# store-column-block.net
KiCad netlist of a schematic drawn in EAGLE
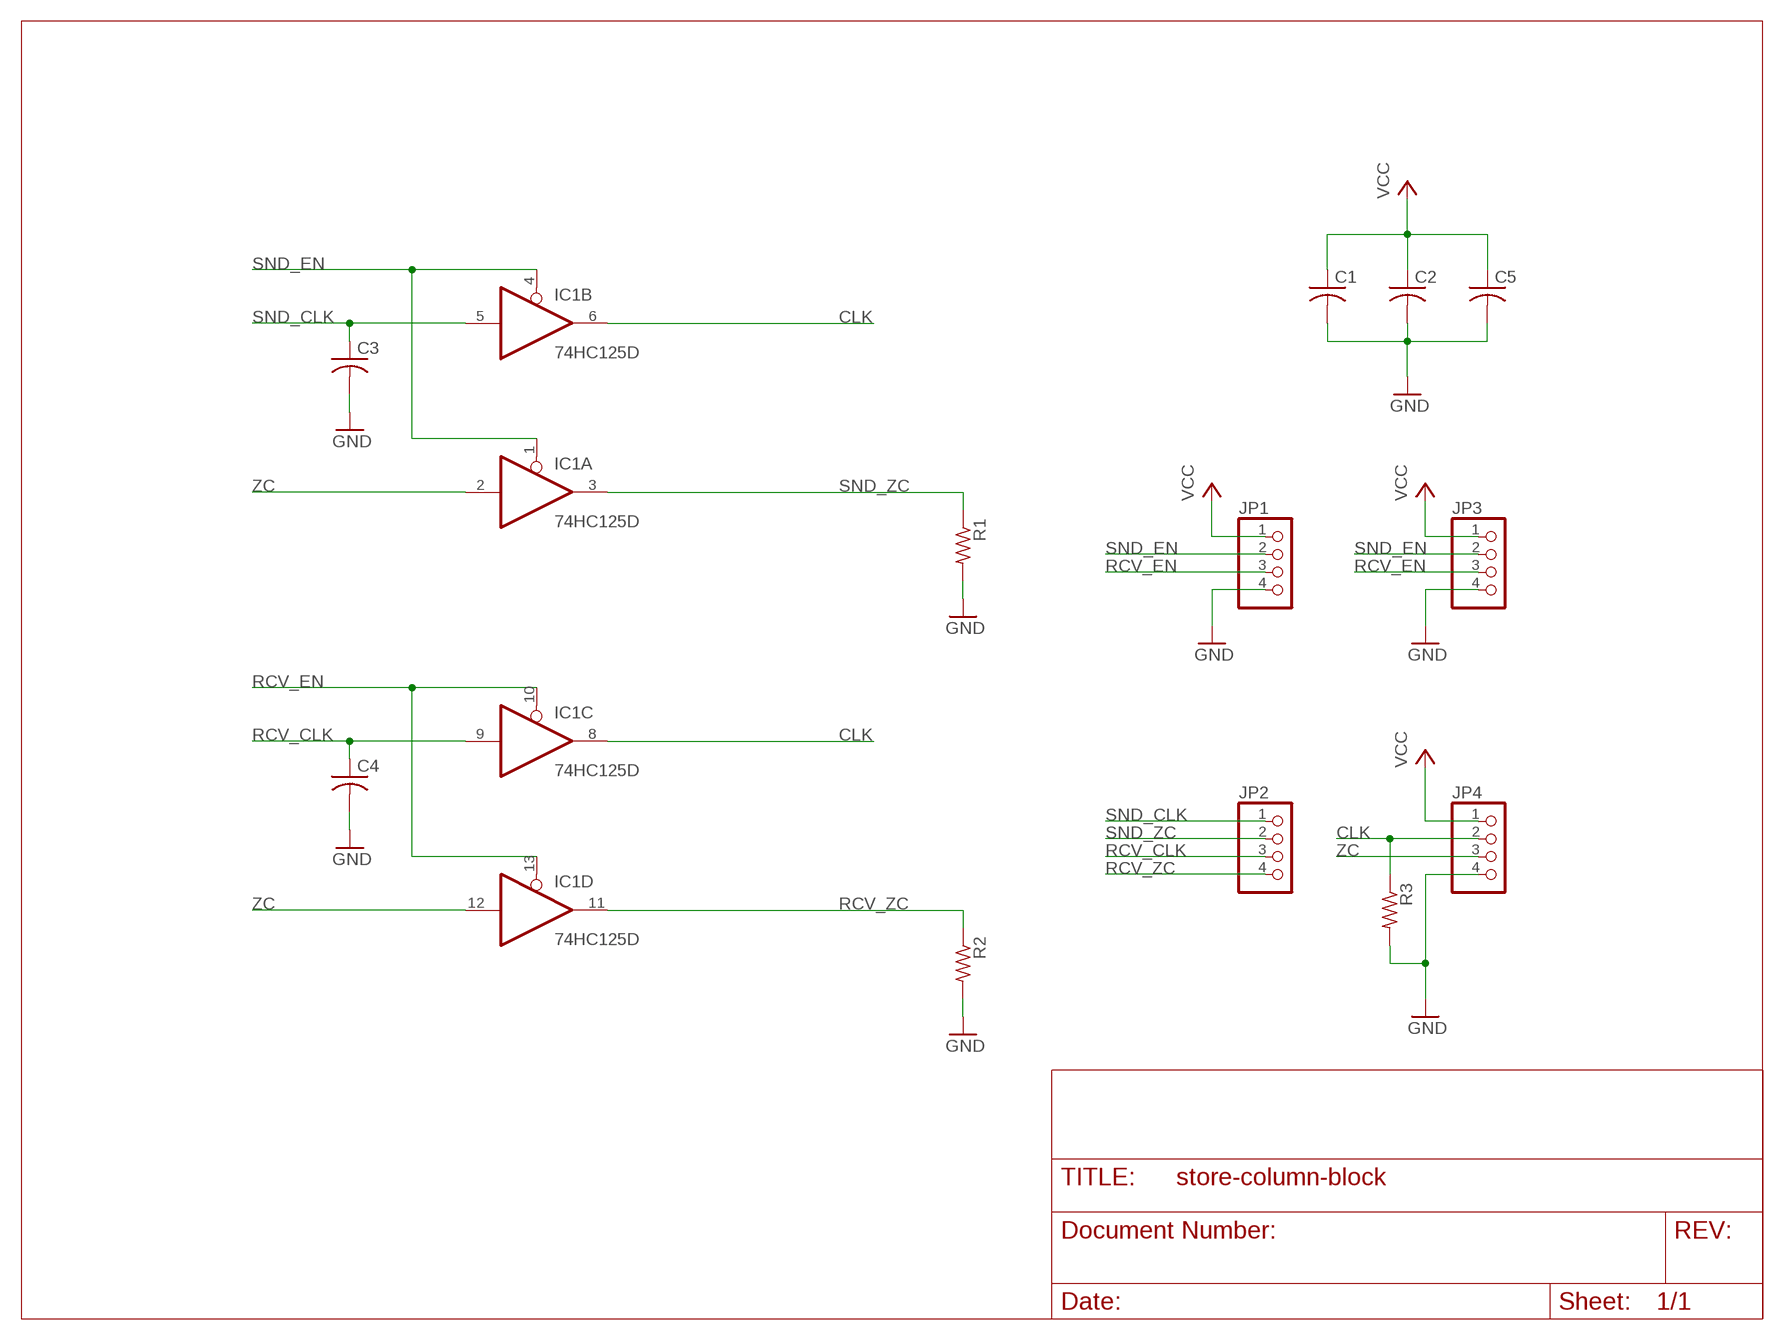
[diagram p0: schematic, sheet 1]

(export (version "E")
  (design (tool "Eeschema 10.0.6"))
  (components
    (comp (ref "C1")
      (value "C-USC0603K")
      (footprint "eagle-import:C0603K")
      (libsource (lib "eagle-import") (part "C-USC0603K"))
    )
    (comp (ref "C2")
      (value "C-USC0603K")
      (footprint "eagle-import:C0603K")
      (libsource (lib "eagle-import") (part "C-USC0603K"))
    )
    (comp (ref "C3")
      (value "C-USC0603K")
      (footprint "eagle-import:C0603K")
      (libsource (lib "eagle-import") (part "C-USC0603K"))
    )
    (comp (ref "C4")
      (value "C-USC0603K")
      (footprint "eagle-import:C0603K")
      (libsource (lib "eagle-import") (part "C-USC0603K"))
    )
    (comp (ref "C5")
      (value "C-USC0603K")
      (footprint "eagle-import:C0603K")
      (libsource (lib "eagle-import") (part "C-USC0603K"))
    )
    (comp (ref "IC1")
      (value "74HC125D")
      (footprint "eagle-import:SO14")
      (libsource (lib "eagle-import") (part "74125DHC"))
    )
    (comp (ref "JP1")
      (value "PINHD-1X4")
      (footprint "eagle-import:1X04")
      (libsource (lib "eagle-import") (part "PINHD-1X4"))
    )
    (comp (ref "JP2")
      (value "PINHD-1X4")
      (footprint "eagle-import:1X04")
      (libsource (lib "eagle-import") (part "PINHD-1X4"))
    )
    (comp (ref "JP3")
      (value "PINHD-1X4")
      (footprint "eagle-import:1X04")
      (libsource (lib "eagle-import") (part "PINHD-1X4"))
    )
    (comp (ref "JP4")
      (value "PINHD-1X4")
      (footprint "eagle-import:1X04")
      (libsource (lib "eagle-import") (part "PINHD-1X4"))
    )
    (comp (ref "R1")
      (value "R-US_R0603")
      (footprint "eagle-import:R0603")
      (libsource (lib "eagle-import") (part "R-US_R0603"))
    )
    (comp (ref "R2")
      (value "R-US_R0603")
      (footprint "eagle-import:R0603")
      (libsource (lib "eagle-import") (part "R-US_R0603"))
    )
    (comp (ref "R3")
      (value "R-US_R0603")
      (footprint "eagle-import:R0603")
      (libsource (lib "eagle-import") (part "R-US_R0603"))
    )
  )
  (nets
    (net (code "1") (name "/CLK") (class "Default")
      (node (ref "IC1") (pin "6") (pinfunction "O_6") (pintype "tri_state"))
      (node (ref "IC1") (pin "8") (pinfunction "O_8") (pintype "tri_state"))
      (node (ref "JP4") (pin "2") (pinfunction "2_2") (pintype "passive"))
      (node (ref "R3") (pin "1") (pinfunction "1_1") (pintype "passive"))
    )
    (net (code "2") (name "/RCV_CLK") (class "Default")
      (node (ref "C4") (pin "1") (pinfunction "1_1") (pintype "passive"))
      (node (ref "IC1") (pin "9") (pinfunction "I_9") (pintype "input"))
      (node (ref "JP2") (pin "3") (pinfunction "3_3") (pintype "passive"))
    )
    (net (code "3") (name "/RCV_EN") (class "Default")
      (node (ref "IC1") (pin "10") (pinfunction "OE_10") (pintype "input"))
      (node (ref "IC1") (pin "13") (pinfunction "OE_13") (pintype "input"))
      (node (ref "JP1") (pin "3") (pinfunction "3_3") (pintype "passive"))
      (node (ref "JP3") (pin "3") (pinfunction "3_3") (pintype "passive"))
    )
    (net (code "4") (name "/RCV_ZC") (class "Default")
      (node (ref "IC1") (pin "11") (pinfunction "O_11") (pintype "tri_state"))
      (node (ref "JP2") (pin "4") (pinfunction "4_4") (pintype "passive"))
      (node (ref "R2") (pin "1") (pinfunction "1_1") (pintype "passive"))
    )
    (net (code "5") (name "/SND_CLK") (class "Default")
      (node (ref "C3") (pin "1") (pinfunction "1_1") (pintype "passive"))
      (node (ref "IC1") (pin "5") (pinfunction "I_5") (pintype "input"))
      (node (ref "JP2") (pin "1") (pinfunction "1_1") (pintype "passive"))
    )
    (net (code "6") (name "/SND_EN") (class "Default")
      (node (ref "IC1") (pin "1") (pinfunction "OE_1") (pintype "input"))
      (node (ref "IC1") (pin "4") (pinfunction "OE_4") (pintype "input"))
      (node (ref "JP1") (pin "2") (pinfunction "2_2") (pintype "passive"))
      (node (ref "JP3") (pin "2") (pinfunction "2_2") (pintype "passive"))
    )
    (net (code "7") (name "/SND_ZC") (class "Default")
      (node (ref "IC1") (pin "3") (pinfunction "O_3") (pintype "tri_state"))
      (node (ref "JP2") (pin "2") (pinfunction "2_2") (pintype "passive"))
      (node (ref "R1") (pin "1") (pinfunction "1_1") (pintype "passive"))
    )
    (net (code "8") (name "/ZC") (class "Default")
      (node (ref "IC1") (pin "12") (pinfunction "I_12") (pintype "input"))
      (node (ref "IC1") (pin "2") (pinfunction "I_2") (pintype "input"))
      (node (ref "JP4") (pin "3") (pinfunction "3_3") (pintype "passive"))
    )
    (net (code "9") (name "GND") (class "Default")
      (node (ref "C1") (pin "2") (pinfunction "2_2") (pintype "passive"))
      (node (ref "C2") (pin "2") (pinfunction "2_2") (pintype "passive"))
      (node (ref "C3") (pin "2") (pinfunction "2_2") (pintype "passive"))
      (node (ref "C4") (pin "2") (pinfunction "2_2") (pintype "passive"))
      (node (ref "C5") (pin "2") (pinfunction "2_2") (pintype "passive"))
      (node (ref "JP1") (pin "4") (pinfunction "4_4") (pintype "passive"))
      (node (ref "JP3") (pin "4") (pinfunction "4_4") (pintype "passive"))
      (node (ref "JP4") (pin "4") (pinfunction "4_4") (pintype "passive"))
      (node (ref "R1") (pin "2") (pinfunction "2_2") (pintype "passive"))
      (node (ref "R2") (pin "2") (pinfunction "2_2") (pintype "passive"))
      (node (ref "R3") (pin "2") (pinfunction "2_2") (pintype "passive"))
    )
    (net (code "10") (name "VCC") (class "Default")
      (node (ref "C1") (pin "1") (pinfunction "1_1") (pintype "passive"))
      (node (ref "C2") (pin "1") (pinfunction "1_1") (pintype "passive"))
      (node (ref "C5") (pin "1") (pinfunction "1_1") (pintype "passive"))
      (node (ref "JP1") (pin "1") (pinfunction "1_1") (pintype "passive"))
      (node (ref "JP3") (pin "1") (pinfunction "1_1") (pintype "passive"))
      (node (ref "JP4") (pin "1") (pinfunction "1_1") (pintype "passive"))
    )
  )
)
